# esp32.net
KiCad netlist of a schematic drawn in Altium Designer
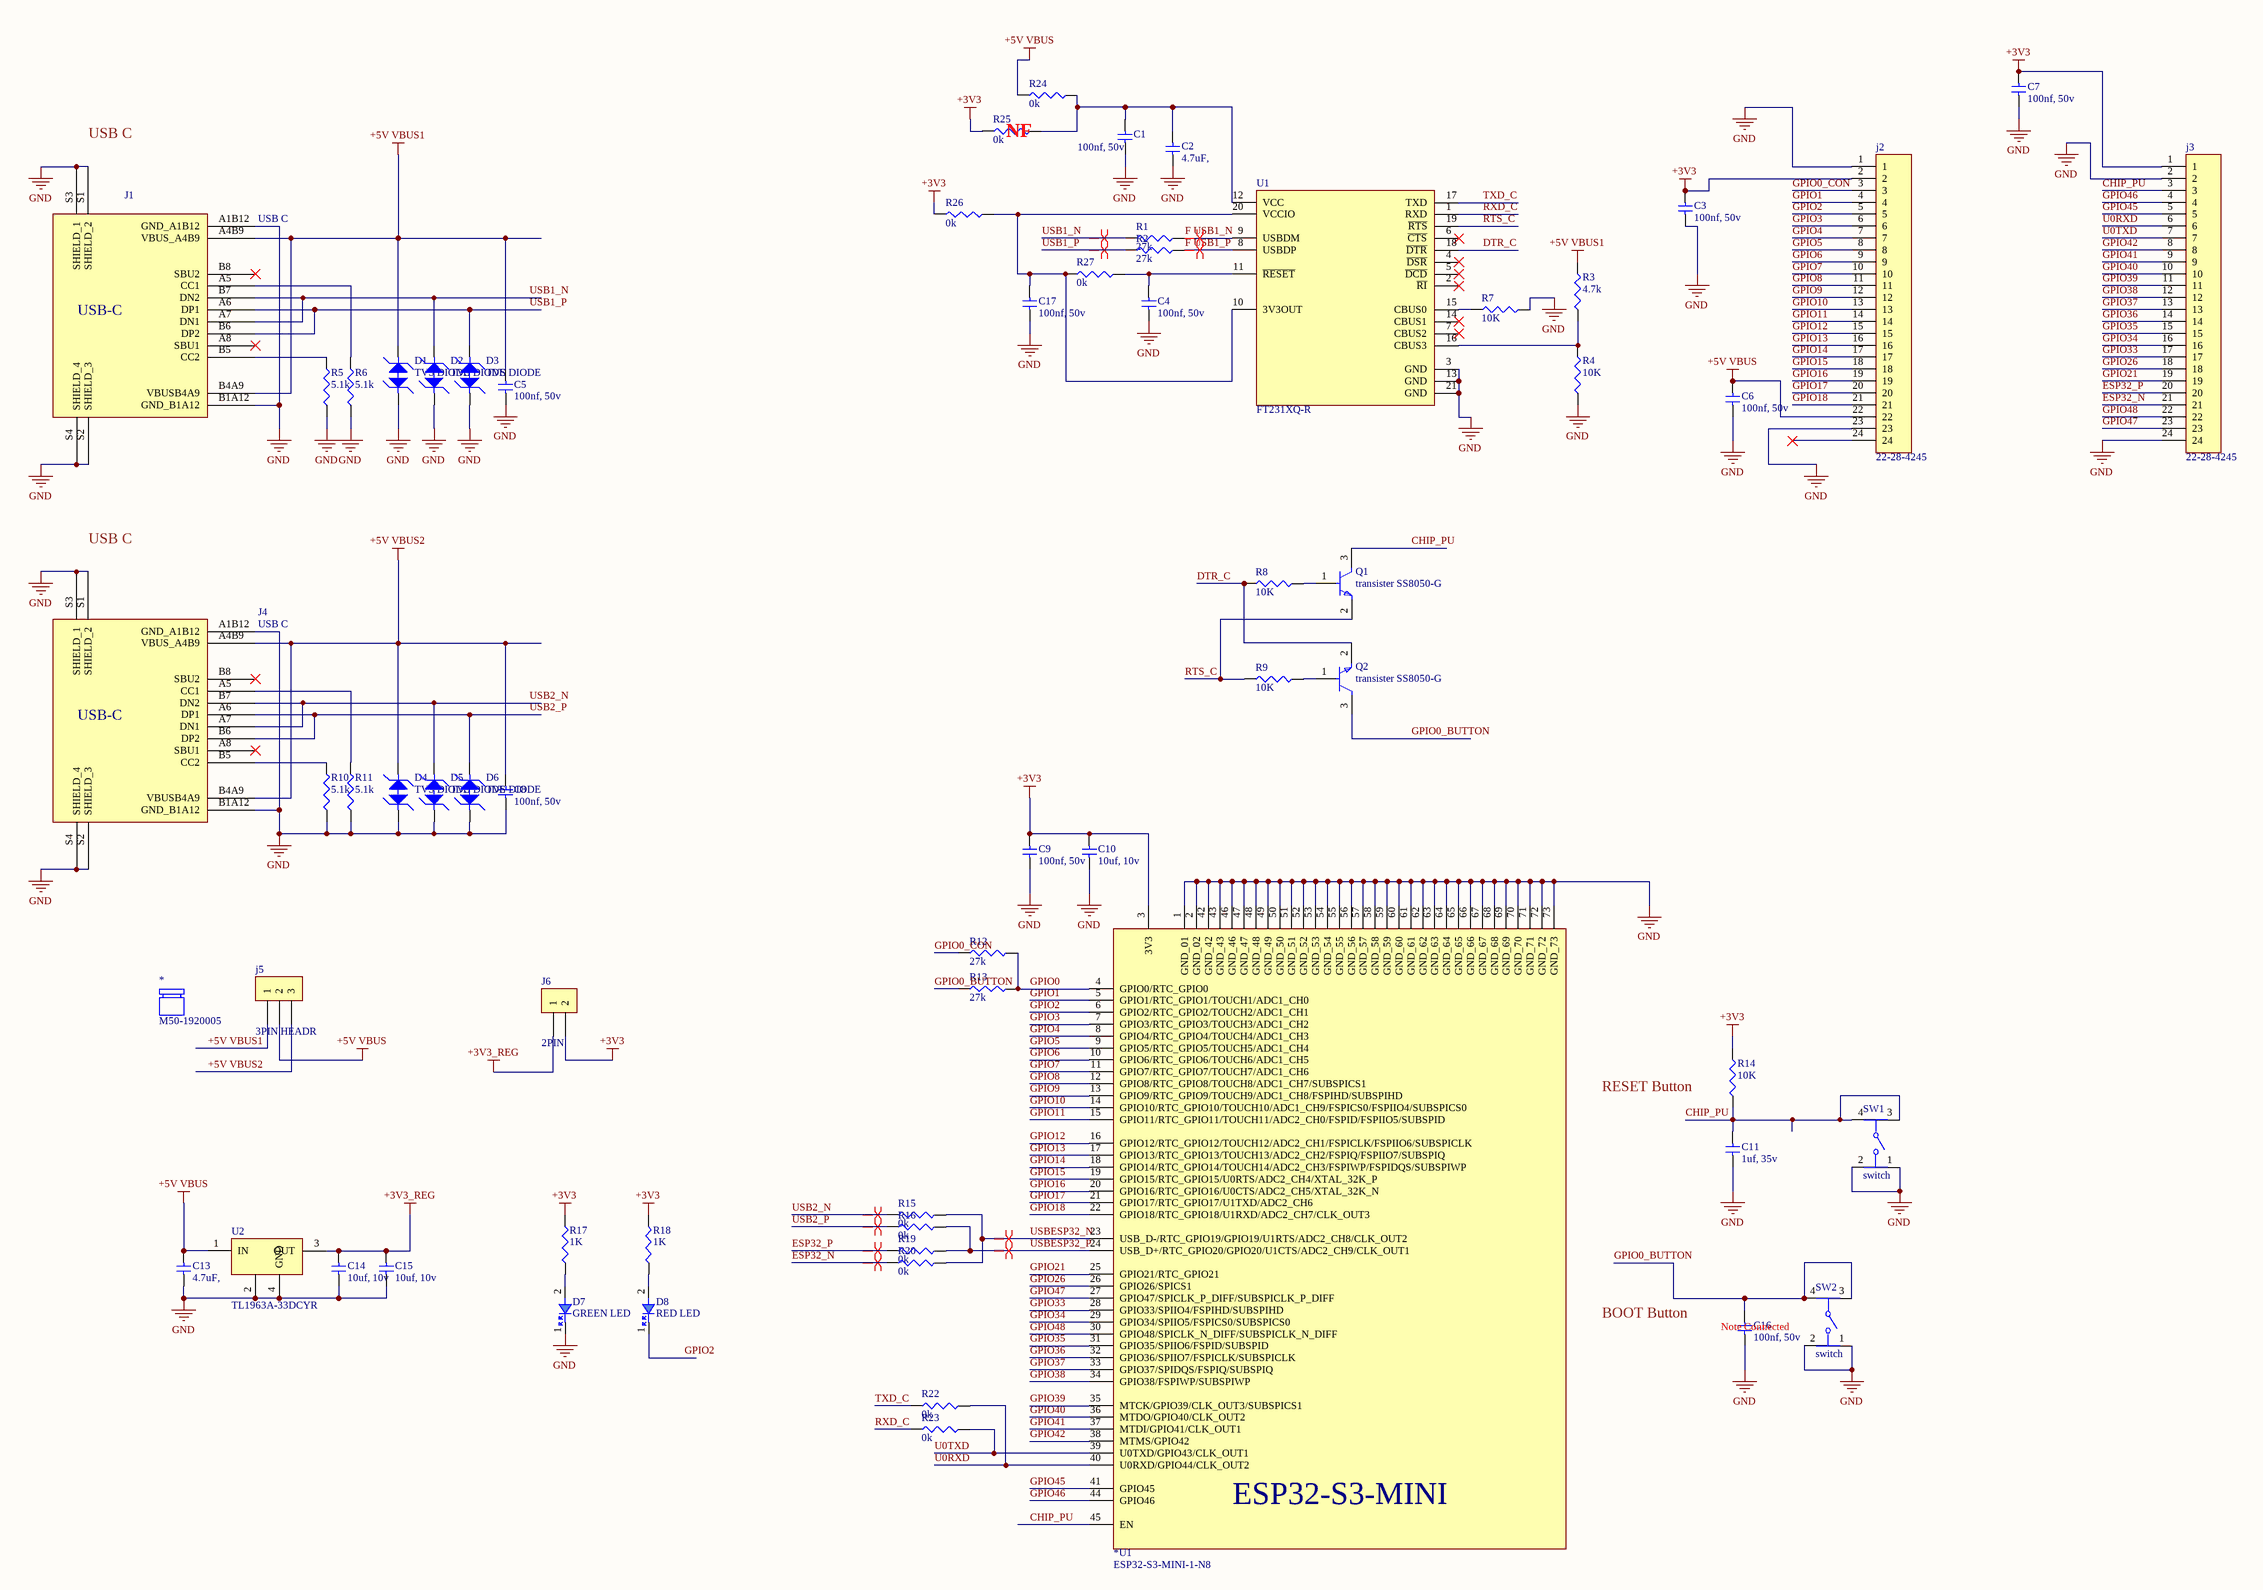
[diagram p0: esp32.SchDoc]

(export (version "E")
  (design (tool "Eeschema 10.0.6"))
  (components
    (comp (ref "*")
      (value "M50-1920005")
      (description "Interconnection Device")
      (fields (field (name "MANUFACTURER") "Harwin"))
      (libsource (lib "esp32") (part "M50-1920005"))
    )
    (comp (ref "*U1")
      (value "ESP32-S3-MINI-1-N8")
      (footprint "ESP32-S3-MINI-1-N8")
      (description "ESP32-S3FN8, 8 MB SPI flash, PCB antenna")
      (fields (field (name "MANUFACTURER") "Espressif Systems") (field (name "LCSC PART NUMBER") "C2913206"))
      (libsource (lib "esp32") (part "ESP32-S3-MINI-1-N8"))
    )
    (comp (ref "C1")
      (value "100nf, 50v")
      (footprint "CAPC1005X06N")
      (description "50V,  0.1uF, Surface Mount, 0402")
      (fields
        (field (name "MANUFACTURER") "Samsung")
        (field (name "MANUFACTURER PART NUMBER") "CL05B104KB5NNNC")
      )
      (libsource (lib "esp32") (part "CL05B104KB5NNNC"))
    )
    (comp (ref "C2")
      (value "4.7uF,")
      (footprint "CAPC1005X06N")
      (fields
        (field (name "MANUFACTURER") "Samsung")
        (field (name "MANUFACTURER PART NUMBER") "CL05A475MO5NUNC")
      )
      (libsource (lib "esp32") (part "CL05A475MO5NUNC"))
    )
    (comp (ref "C3")
      (value "100nf, 50v")
      (footprint "CAPC1005X06N")
      (description "50V,  0.1uF, Surface Mount, 0402")
      (fields
        (field (name "MANUFACTURER") "Samsung")
        (field (name "MANUFACTURER PART NUMBER") "CL05B104KB5NNNC")
      )
      (libsource (lib "esp32") (part "CL05B104KB5NNNC"))
    )
    (comp (ref "C4")
      (value "100nf, 50v")
      (footprint "CAPC1005X06N")
      (description "50V,  0.1uF, Surface Mount, 0402")
      (fields
        (field (name "MANUFACTURER") "Samsung")
        (field (name "MANUFACTURER PART NUMBER") "CL05B104KB5NNNC")
      )
      (libsource (lib "esp32") (part "CL05B104KB5NNNC"))
    )
    (comp (ref "C5")
      (value "100nf, 50v")
      (footprint "CAPC1005X06N")
      (description "50V,  0.1uF, Surface Mount, 0402")
      (fields
        (field (name "MANUFACTURER") "Samsung")
        (field (name "MANUFACTURER PART NUMBER") "CL05B104KB5NNNC")
      )
      (libsource (lib "esp32") (part "CL05B104KB5NNNC"))
    )
    (comp (ref "C6")
      (value "100nf, 50v")
      (footprint "CAPC1005X06N")
      (description "50V,  0.1uF, Surface Mount, 0402")
      (fields
        (field (name "MANUFACTURER") "Samsung")
        (field (name "MANUFACTURER PART NUMBER") "CL05B104KB5NNNC")
      )
      (libsource (lib "esp32") (part "CL05B104KB5NNNC"))
    )
    (comp (ref "C7")
      (value "100nf, 50v")
      (footprint "CAPC1005X06N")
      (description "50V,  0.1uF, Surface Mount, 0402")
      (fields
        (field (name "MANUFACTURER") "Samsung")
        (field (name "MANUFACTURER PART NUMBER") "CL05B104KB5NNNC")
      )
      (libsource (lib "esp32") (part "CL05B104KB5NNNC"))
    )
    (comp (ref "C8")
      (value "100nf, 50v")
      (footprint "CAPC1005X06N")
      (description "50V,  0.1uF, Surface Mount, 0402")
      (fields
        (field (name "MANUFACTURER") "Samsung")
        (field (name "MANUFACTURER PART NUMBER") "CL05B104KB5NNNC")
      )
      (libsource (lib "esp32") (part "CL05B104KB5NNNC"))
    )
    (comp (ref "C9")
      (value "100nf, 50v")
      (footprint "CAPC1005X06N")
      (description "50V,  0.1uF, Surface Mount, 0402")
      (fields
        (field (name "MANUFACTURER") "Samsung")
        (field (name "MANUFACTURER PART NUMBER") "CL05B104KB5NNNC")
      )
      (libsource (lib "esp32") (part "CL05B104KB5NNNC"))
    )
    (comp (ref "C10")
      (value "10uf, 10v")
      (footprint "CAPC1005X06N")
      (description "10V,10uF, Surface Mount, 0402")
      (fields
        (field (name "MANUFACTURER") "Samsung")
        (field (name "MANUFACTURER PART NUMBER") "CL05A106MP5NRNC")
      )
      (libsource (lib "esp32") (part "CL05A106MP5NRNC"))
    )
    (comp (ref "C11")
      (value "1uf, 35v")
      (footprint "CAPC1005X06N")
      (description "35V, 1uF, Surface Mount, 0402")
      (fields
        (field (name "MANUFACTURER") "Samsung")
        (field (name "MANUFACTURER PART NUMBER") "CL05A105KL5NRNC")
      )
      (libsource (lib "esp32") (part "CL05A105KL5NRNC"))
    )
    (comp (ref "C13")
      (value "4.7uF,")
      (footprint "CAPC1005X06N")
      (fields
        (field (name "MANUFACTURER") "Samsung")
        (field (name "MANUFACTURER PART NUMBER") "CL05A475MO5NUNC")
      )
      (libsource (lib "esp32") (part "CL05A475MO5NUNC"))
    )
    (comp (ref "C14")
      (value "10uf, 10v")
      (footprint "CAPC1005X06N")
      (description "10V,10uF, Surface Mount, 0402")
      (fields
        (field (name "MANUFACTURER") "Samsung")
        (field (name "MANUFACTURER PART NUMBER") "CL05A106MP5NRNC")
      )
      (libsource (lib "esp32") (part "CL05A106MP5NRNC"))
    )
    (comp (ref "C15")
      (value "10uf, 10v")
      (footprint "CAPC1005X06N")
      (description "10V,10uF, Surface Mount, 0402")
      (fields
        (field (name "MANUFACTURER") "Samsung")
        (field (name "MANUFACTURER PART NUMBER") "CL05A106MP5NRNC")
      )
      (libsource (lib "esp32") (part "CL05A106MP5NRNC"))
    )
    (comp (ref "C16")
      (value "100nf, 50v")
      (footprint "CAPC1005X06N")
      (description "50V,  0.1uF, Surface Mount, 0402")
      (fields
        (field (name "MANUFACTURER") "Samsung")
        (field (name "MANUFACTURER PART NUMBER") "CL05B104KB5NNNC")
      )
      (libsource (lib "esp32") (part "CL05B104KB5NNNC"))
    )
    (comp (ref "C17")
      (value "100nf, 50v")
      (footprint "CAPC1005X06N")
      (description "50V,  0.1uF, Surface Mount, 0402")
      (fields
        (field (name "MANUFACTURER") "Samsung")
        (field (name "MANUFACTURER PART NUMBER") "CL05B104KB5NNNC")
      )
      (libsource (lib "esp32") (part "CL05B104KB5NNNC"))
    )
    (comp (ref "D1")
      (value "TVS DIODE")
      (footprint "tv Diode")
      (description "Trans Voltage Suppressor Diode, 40W, 5.3V V(RWM), Bidirectional, 1 Element, Silicon, MO-236")
      (fields
        (field (name "MANUFACTURER") "Littelfuse")
        (field (name "MANUFACTURER PART NUMBER") "AQ3045-01ETG")
      )
      (libsource (lib "esp32") (part "AQ3045-01ETG"))
    )
    (comp (ref "D2")
      (value "TVS DIODE")
      (footprint "tv Diode")
      (description "Trans Voltage Suppressor Diode, 40W, 5.3V V(RWM), Bidirectional, 1 Element, Silicon, MO-236")
      (fields
        (field (name "MANUFACTURER") "Littelfuse")
        (field (name "MANUFACTURER PART NUMBER") "AQ3045-01ETG")
      )
      (libsource (lib "esp32") (part "AQ3045-01ETG"))
    )
    (comp (ref "D3")
      (value "TVS DIODE")
      (footprint "tv Diode")
      (description "Trans Voltage Suppressor Diode, 40W, 5.3V V(RWM), Bidirectional, 1 Element, Silicon, MO-236")
      (fields
        (field (name "MANUFACTURER") "Littelfuse")
        (field (name "MANUFACTURER PART NUMBER") "AQ3045-01ETG")
      )
      (libsource (lib "esp32") (part "AQ3045-01ETG"))
    )
    (comp (ref "D4")
      (value "TVS DIODE")
      (footprint "tv Diode")
      (description "Trans Voltage Suppressor Diode, 40W, 5.3V V(RWM), Bidirectional, 1 Element, Silicon, MO-236")
      (fields
        (field (name "MANUFACTURER") "Littelfuse")
        (field (name "MANUFACTURER PART NUMBER") "AQ3045-01ETG")
      )
      (libsource (lib "esp32") (part "AQ3045-01ETG"))
    )
    (comp (ref "D5")
      (value "TVS DIODE")
      (footprint "tv Diode")
      (description "Trans Voltage Suppressor Diode, 40W, 5.3V V(RWM), Bidirectional, 1 Element, Silicon, MO-236")
      (fields
        (field (name "MANUFACTURER") "Littelfuse")
        (field (name "MANUFACTURER PART NUMBER") "AQ3045-01ETG")
      )
      (libsource (lib "esp32") (part "AQ3045-01ETG"))
    )
    (comp (ref "D6")
      (value "TVS DIODE")
      (footprint "tv Diode")
      (description "Trans Voltage Suppressor Diode, 40W, 5.3V V(RWM), Bidirectional, 1 Element, Silicon, MO-236")
      (fields
        (field (name "MANUFACTURER") "Littelfuse")
        (field (name "MANUFACTURER PART NUMBER") "AQ3045-01ETG")
      )
      (libsource (lib "esp32") (part "AQ3045-01ETG"))
    )
    (comp (ref "D7")
      (value "GREEN LED")
      (footprint "led green")
      (description "Single Color LED, Yellow Green, 0.5mm")
      (fields
        (field (name "MANUFACTURER") "Vishay")
        (field (name "MANUFACTURER PART NUMBER") "VLMG1500-GS08")
      )
      (libsource (lib "esp32") (part "VLMG1500-GS08"))
    )
    (comp (ref "D8")
      (value "RED LED")
      (footprint "red led")
      (description "Single Color LED, Yellow Green, 0.5mm")
      (fields
        (field (name "MANUFACTURER") "Vishay")
        (field (name "MANUFACTURER PART NUMBER") "VLMG1500-GS08")
      )
      (libsource (lib "esp32") (part "VLMG1500-GS08_1"))
    )
    (comp (ref "J1")
      (value "USB C")
      (footprint "usb_c")
      (description "USB Connector, 16 Contact(s), Female, Right Angle, Surface Mount Terminal, Locking, Receptacle")
      (fields (field (name "MANUFACTURER") "Molex") (field (name "MANUFACTURER PART NUMBER") "217179-0001"))
      (libsource (lib "esp32") (part "217179-0001"))
    )
    (comp (ref "j2")
      (value "22-28-4245")
      (footprint "pin 24 2.54mm")
      (description "Conn Unshrouded Header HDR 24 POS 2.54mm Solder ST Thru-Hole KK® Bag")
      (fields (field (name "MANUFACTURER") "Molex"))
      (libsource (lib "esp32") (part "22-28-4245"))
    )
    (comp (ref "j3")
      (value "22-28-4245")
      (footprint "pin 24 2.54mm")
      (description "Conn Unshrouded Header HDR 24 POS 2.54mm Solder ST Thru-Hole KK® Bag")
      (fields (field (name "MANUFACTURER") "Molex"))
      (libsource (lib "esp32") (part "22-28-4245"))
    )
    (comp (ref "J4")
      (value "USB C")
      (footprint "usb_c")
      (description "USB Connector, 16 Contact(s), Female, Right Angle, Surface Mount Terminal, Locking, Receptacle")
      (fields (field (name "MANUFACTURER") "Molex") (field (name "MANUFACTURER PART NUMBER") "217179-0001"))
      (libsource (lib "esp32") (part "217179-0001"))
    )
    (comp (ref "j5")
      (value "3PIN HEADR")
      (footprint "pin3")
      (description "Board Connector, 3 Contact(s), 1 Row(s), Male, Straight, Solder Terminal")
      (fields
        (field (name "MANUFACTURER") "Samtec")
        (field (name "MANUFACTURER PART NUMBER") "FTS-103-01-F-S")
      )
      (libsource (lib "esp32") (part "FTS-103-01-F-S"))
    )
    (comp (ref "J6")
      (value "2PIN")
      (footprint "pin2")
      (description "Board Connector, 2 Contact(s), 1 Row(s), Male, Straight, Solder Terminal")
      (fields
        (field (name "MANUFACTURER") "Samtec")
        (field (name "MANUFACTURER PART NUMBER") "FTS-102-01-F-S")
      )
      (libsource (lib "esp32") (part "FTS-102-01-F-S"))
    )
    (comp (ref "Q1")
      (value "transister SS8050-G")
      (footprint "transister")
      (description "Small Signal Bipolar Transistor, 1.5A I(C), 25V V(BR)CEO, 1-Element, NPN, Silicon")
      (fields (field (name "MANUFACTURER") "Comchip") (field (name "MANUFACTURER PART NUMBER") "SS8050-G"))
      (libsource (lib "esp32") (part "SS8050-G"))
    )
    (comp (ref "Q2")
      (value "transister SS8050-G")
      (footprint "transister")
      (description "Small Signal Bipolar Transistor, 1.5A I(C), 25V V(BR)CEO, 1-Element, NPN, Silicon")
      (fields (field (name "MANUFACTURER") "Comchip") (field (name "MANUFACTURER PART NUMBER") "SS8050-G"))
      (libsource (lib "esp32") (part "SS8050-G"))
    )
    (comp (ref "R1")
      (value "27k")
      (footprint "RESC1005X04N")
      (description "27k,Fixed Resistor 0.0625W, , 50V, Surface Mount, 0402")
      (fields
        (field (name "MANUFACTURER") "Yageo")
        (field (name "MANUFACTURER PART NUMBER") "AC0402FR-0727KL")
      )
      (libsource (lib "esp32") (part "AC0402FR-0727KL"))
    )
    (comp (ref "R2")
      (value "27k")
      (footprint "RESC1005X04N")
      (description "27k,Fixed Resistor 0.0625W, , 50V, Surface Mount, 0402")
      (fields
        (field (name "MANUFACTURER") "Yageo")
        (field (name "MANUFACTURER PART NUMBER") "AC0402FR-0727KL")
      )
      (libsource (lib "esp32") (part "AC0402FR-0727KL"))
    )
    (comp (ref "R3")
      (value "4.7k")
      (footprint "RESC1005X04N")
      (fields
        (field (name "MANUFACTURER") "Yageo")
        (field (name "MANUFACTURER PART NUMBER") "RC0402JR-074K7L")
        (field (name "TOLERANCE") "5%")
      )
      (libsource (lib "esp32") (part "RC0402JR-074K7L"))
    )
    (comp (ref "R4")
      (value "10K")
      (footprint "RESC1005X04N")
      (description "0.125W, 10kohm, 75V, Surface Mount, 0402")
      (fields
        (field (name "MANUFACTURER") "Yageo")
        (field (name "MANUFACTURER PART NUMBER") "AC0402FR-7W10KL")
      )
      (libsource (lib "esp32") (part "AC0402FR-7W10KL"))
    )
    (comp (ref "R5")
      (value "5.1k")
      (footprint "RESC1005X04N")
      (description "Resistor 0.0625W, 5.1Kohm, 50V, 1% +/-Tol, 100ppm/Cel, Surface Mount, 0402")
      (fields
        (field (name "MANUFACTURER") "Yageo")
        (field (name "MANUFACTURER PART NUMBER") "AC0402FR-075K1L")
      )
      (libsource (lib "esp32") (part "AC0402FR-075K1L"))
    )
    (comp (ref "R6")
      (value "5.1k")
      (footprint "RESC1005X04N")
      (description "Resistor 0.0625W, 5.1Kohm, 50V, 1% +/-Tol, 100ppm/Cel, Surface Mount, 0402")
      (fields
        (field (name "MANUFACTURER") "Yageo")
        (field (name "MANUFACTURER PART NUMBER") "AC0402FR-075K1L")
      )
      (libsource (lib "esp32") (part "AC0402FR-075K1L"))
    )
    (comp (ref "R7")
      (value "10K")
      (footprint "RESC1005X04N")
      (description "0.125W, 10kohm, 75V, Surface Mount, 0402")
      (fields
        (field (name "MANUFACTURER") "Yageo")
        (field (name "MANUFACTURER PART NUMBER") "AC0402FR-7W10KL")
      )
      (libsource (lib "esp32") (part "AC0402FR-7W10KL"))
    )
    (comp (ref "R8")
      (value "10K")
      (footprint "RESC1005X04N")
      (description "0.125W, 10kohm, 75V, Surface Mount, 0402")
      (fields
        (field (name "MANUFACTURER") "Yageo")
        (field (name "MANUFACTURER PART NUMBER") "AC0402FR-7W10KL")
      )
      (libsource (lib "esp32") (part "AC0402FR-7W10KL"))
    )
    (comp (ref "R9")
      (value "10K")
      (footprint "RESC1005X04N")
      (description "0.125W, 10kohm, 75V, Surface Mount, 0402")
      (fields
        (field (name "MANUFACTURER") "Yageo")
        (field (name "MANUFACTURER PART NUMBER") "AC0402FR-7W10KL")
      )
      (libsource (lib "esp32") (part "AC0402FR-7W10KL"))
    )
    (comp (ref "R10")
      (value "5.1k")
      (footprint "RESC1005X04N")
      (description "Resistor 0.0625W, 5.1Kohm, 50V, 1% +/-Tol, 100ppm/Cel, Surface Mount, 0402")
      (fields
        (field (name "MANUFACTURER") "Yageo")
        (field (name "MANUFACTURER PART NUMBER") "AC0402FR-075K1L")
      )
      (libsource (lib "esp32") (part "AC0402FR-075K1L"))
    )
    (comp (ref "R11")
      (value "5.1k")
      (footprint "RESC1005X04N")
      (description "Resistor 0.0625W, 5.1Kohm, 50V, 1% +/-Tol, 100ppm/Cel, Surface Mount, 0402")
      (fields
        (field (name "MANUFACTURER") "Yageo")
        (field (name "MANUFACTURER PART NUMBER") "AC0402FR-075K1L")
      )
      (libsource (lib "esp32") (part "AC0402FR-075K1L"))
    )
    (comp (ref "R12")
      (value "27k")
      (footprint "RESC1005X04N")
      (description "27k,Fixed Resistor 0.0625W, , 50V, Surface Mount, 0402")
      (fields
        (field (name "MANUFACTURER") "Yageo")
        (field (name "MANUFACTURER PART NUMBER") "AC0402FR-0727KL")
      )
      (libsource (lib "esp32") (part "AC0402FR-0727KL"))
    )
    (comp (ref "R13")
      (value "27k")
      (footprint "RESC1005X04N")
      (description "27k,Fixed Resistor 0.0625W, , 50V, Surface Mount, 0402")
      (fields
        (field (name "MANUFACTURER") "Yageo")
        (field (name "MANUFACTURER PART NUMBER") "AC0402FR-0727KL")
      )
      (libsource (lib "esp32") (part "AC0402FR-0727KL"))
    )
    (comp (ref "R14")
      (value "10K")
      (footprint "RESC1005X04N")
      (description "0.125W, 10kohm, 75V, Surface Mount, 0402")
      (fields
        (field (name "MANUFACTURER") "Yageo")
        (field (name "MANUFACTURER PART NUMBER") "AC0402FR-7W10KL")
      )
      (libsource (lib "esp32") (part "AC0402FR-7W10KL"))
    )
    (comp (ref "R15")
      (value "0k")
      (footprint "RESC1005X04N")
      (description "0.0625W, 0ohm, Surface Mount, 0402")
      (fields
        (field (name "MANUFACTURER") "Yageo")
        (field (name "MANUFACTURER PART NUMBER") "RC0402FR-070RL")
      )
      (libsource (lib "esp32") (part "RC0402FR-070RL"))
    )
    (comp (ref "R16")
      (value "0k")
      (footprint "RESC1005X04N")
      (description "0.0625W, 0ohm, Surface Mount, 0402")
      (fields
        (field (name "MANUFACTURER") "Yageo")
        (field (name "MANUFACTURER PART NUMBER") "RC0402FR-070RL")
      )
      (libsource (lib "esp32") (part "RC0402FR-070RL"))
    )
    (comp (ref "R17")
      (value "1K")
      (footprint "RESC1005X04N")
      (fields
        (field (name "MANUFACTURER") "Yageo")
        (field (name "MANUFACTURER PART NUMBER") "RC0402FR-071KL")
        (field (name "TOLERANCE") "1%")
      )
      (libsource (lib "esp32") (part "RC0402FR-071KL"))
    )
    (comp (ref "R18")
      (value "1K")
      (footprint "RESC1005X04N")
      (fields
        (field (name "MANUFACTURER") "Yageo")
        (field (name "MANUFACTURER PART NUMBER") "RC0402FR-071KL")
        (field (name "TOLERANCE") "1%")
      )
      (libsource (lib "esp32") (part "RC0402FR-071KL"))
    )
    (comp (ref "R19")
      (value "0k")
      (footprint "RESC1005X04N")
      (description "0.0625W, 0ohm, Surface Mount, 0402")
      (fields
        (field (name "MANUFACTURER") "Yageo")
        (field (name "MANUFACTURER PART NUMBER") "RC0402FR-070RL")
      )
      (libsource (lib "esp32") (part "RC0402FR-070RL"))
    )
    (comp (ref "R20")
      (value "0k")
      (footprint "RESC1005X04N")
      (description "0.0625W, 0ohm, Surface Mount, 0402")
      (fields
        (field (name "MANUFACTURER") "Yageo")
        (field (name "MANUFACTURER PART NUMBER") "RC0402FR-070RL")
      )
      (libsource (lib "esp32") (part "RC0402FR-070RL"))
    )
    (comp (ref "R22")
      (value "0k")
      (footprint "RESC1005X04N")
      (description "0.0625W, 0ohm, Surface Mount, 0402")
      (fields
        (field (name "MANUFACTURER") "Yageo")
        (field (name "MANUFACTURER PART NUMBER") "RC0402FR-070RL")
      )
      (libsource (lib "esp32") (part "RC0402FR-070RL"))
    )
    (comp (ref "R23")
      (value "0k")
      (footprint "RESC1005X04N")
      (description "0.0625W, 0ohm, Surface Mount, 0402")
      (fields
        (field (name "MANUFACTURER") "Yageo")
        (field (name "MANUFACTURER PART NUMBER") "RC0402FR-070RL")
      )
      (libsource (lib "esp32") (part "RC0402FR-070RL"))
    )
    (comp (ref "R24")
      (value "0k")
      (footprint "RESC1005X04N")
      (description "0.0625W, 0ohm, Surface Mount, 0402")
      (fields
        (field (name "MANUFACTURER") "Yageo")
        (field (name "MANUFACTURER PART NUMBER") "RC0402FR-070RL")
      )
      (libsource (lib "esp32") (part "RC0402FR-070RL"))
    )
    (comp (ref "R25")
      (value "0k")
      (footprint "RESC1005X04N")
      (description "0.0625W, 0ohm, Surface Mount, 0402")
      (fields
        (field (name "MANUFACTURER") "Yageo")
        (field (name "MANUFACTURER PART NUMBER") "RC0402FR-070RL")
      )
      (libsource (lib "esp32") (part "RC0402FR-070RL"))
    )
    (comp (ref "R26")
      (value "0k")
      (footprint "RESC1005X04N")
      (description "0.0625W, 0ohm, Surface Mount, 0402")
      (fields
        (field (name "MANUFACTURER") "Yageo")
        (field (name "MANUFACTURER PART NUMBER") "RC0402FR-070RL")
      )
      (libsource (lib "esp32") (part "RC0402FR-070RL"))
    )
    (comp (ref "R27")
      (value "0k")
      (footprint "RESC1005X04N")
      (description "0.0625W, 0ohm, Surface Mount, 0402")
      (fields
        (field (name "MANUFACTURER") "Yageo")
        (field (name "MANUFACTURER PART NUMBER") "RC0402FR-070RL")
      )
      (libsource (lib "esp32") (part "RC0402FR-070RL"))
    )
    (comp (ref "SW1")
      (value "switch")
      (footprint "button")
      (description "Keypad Switch, 0.05A, 12VDC, 2.55N, , Surface Mount-straight")
      (fields
        (field (name "MANUFACTURER") "ITT C&K")
        (field (name "MANUFACTURER PART NUMBER") "PTS645SK43SMTR92LFS")
      )
      (libsource (lib "esp32") (part "PTS645SK43SMTR92LFS"))
    )
    (comp (ref "SW2")
      (value "switch")
      (footprint "button")
      (description "Keypad Switch, 0.05A, 12VDC, 2.55N, , Surface Mount-straight")
      (fields
        (field (name "MANUFACTURER") "ITT C&K")
        (field (name "MANUFACTURER PART NUMBER") "PTS645SK43SMTR92LFS")
      )
      (libsource (lib "esp32") (part "PTS645SK43SMTR92LFS"))
    )
    (comp (ref "U1")
      (value "FT231XQ-R")
      (footprint "QFN50P400X400X80_HS-21N")
      (description "IC USB SERIAL FULL UART 20QFN")
      (fields (field (name "MANUFACTURER") "FTDI"))
      (libsource (lib "esp32") (part "FT231XQ-R"))
    )
    (comp (ref "U2")
      (value "TL1963A-33DCYR")
      (footprint "SOT230P700X180-4N")
      (description "Fixed Positive LDO Regulator, 3.3V, 0.55V Dropout, BIPolar, PDSO4")
      (fields (field (name "MANUFACTURER") "Texas Instruments"))
      (libsource (lib "esp32") (part "Regulato TL1963A-33DCYR"))
    )
  )
  (nets
    (net (code "1") (name "+3V3") (class "Default")
      (node (ref "*U1") (pin "3") (pinfunction "3V3_3") (pintype "passive"))
      (node (ref "C10") (pin "2") (pinfunction "2_2") (pintype "open_collector"))
      (node (ref "C3") (pin "2") (pinfunction "2_2") (pintype "open_collector"))
      (node (ref "C7") (pin "2") (pinfunction "2_2") (pintype "open_collector"))
      (node (ref "C9") (pin "2") (pinfunction "2_2") (pintype "open_collector"))
      (node (ref "J6") (pin "2") (pinfunction "2_2") (pintype "open_collector"))
      (node (ref "R14") (pin "2") (pinfunction "2_2") (pintype "open_collector"))
      (node (ref "R17") (pin "2") (pinfunction "2_2") (pintype "open_collector"))
      (node (ref "R18") (pin "2") (pinfunction "2_2") (pintype "open_collector"))
      (node (ref "R25") (pin "1") (pinfunction "1_1") (pintype "open_collector"))
      (node (ref "R26") (pin "1") (pinfunction "1_1") (pintype "open_collector"))
      (node (ref "j2") (pin "2") (pinfunction "2_2") (pintype "passive"))
      (node (ref "j3") (pin "1") (pinfunction "1_1") (pintype "passive"))
    )
    (net (code "2") (name "+3V3_REG") (class "Default")
      (node (ref "C14") (pin "2") (pinfunction "2_2") (pintype "open_collector"))
      (node (ref "C15") (pin "2") (pinfunction "2_2") (pintype "open_collector"))
      (node (ref "J6") (pin "1") (pinfunction "1_1") (pintype "open_collector"))
      (node (ref "U2") (pin "3") (pinfunction "OUT_3") (pintype "passive"))
    )
    (net (code "3") (name "+5V VBUS") (class "Default")
      (node (ref "C13") (pin "2") (pinfunction "2_2") (pintype "open_collector"))
      (node (ref "C6") (pin "2") (pinfunction "2_2") (pintype "open_collector"))
      (node (ref "R24") (pin "1") (pinfunction "1_1") (pintype "open_collector"))
      (node (ref "U2") (pin "1") (pinfunction "IN_1") (pintype "passive"))
      (node (ref "j2") (pin "22") (pinfunction "22_22") (pintype "passive"))
      (node (ref "j5") (pin "2") (pinfunction "2_2") (pintype "open_collector"))
    )
    (net (code "4") (name "+5V VBUS1") (class "Default")
      (node (ref "C5") (pin "2") (pinfunction "2_2") (pintype "open_collector"))
      (node (ref "D1") (pin "2") (pinfunction "2_2") (pintype "open_collector"))
      (node (ref "J1") (pin "A4B9") (pinfunction "VBUS_A4B9_A4B9") (pintype "passive"))
      (node (ref "J1") (pin "B4A9") (pinfunction "VBUSB4A9_B4A9") (pintype "passive"))
      (node (ref "R3") (pin "2") (pinfunction "2_2") (pintype "open_collector"))
      (node (ref "j5") (pin "1") (pinfunction "1_1") (pintype "open_collector"))
    )
    (net (code "5") (name "+5V VBUS2") (class "Default")
      (node (ref "C8") (pin "2") (pinfunction "2_2") (pintype "open_collector"))
      (node (ref "D4") (pin "2") (pinfunction "2_2") (pintype "open_collector"))
      (node (ref "J4") (pin "A4B9") (pinfunction "VBUS_A4B9_A4B9") (pintype "passive"))
      (node (ref "J4") (pin "B4A9") (pinfunction "VBUSB4A9_B4A9") (pintype "passive"))
      (node (ref "j5") (pin "3") (pinfunction "3_3") (pintype "open_collector"))
    )
    (net (code "6") (name "/CHIP_PU") (class "Default")
      (node (ref "*U1") (pin "45") (pinfunction "EN_45") (pintype "passive"))
      (node (ref "C11") (pin "2") (pinfunction "2_2") (pintype "open_collector"))
      (node (ref "Q1") (pin "3") (pinfunction "C_3") (pintype "passive"))
      (node (ref "R14") (pin "1") (pinfunction "1_1") (pintype "open_collector"))
      (node (ref "SW1") (pin "3") (pinfunction "3_3") (pintype "passive"))
      (node (ref "SW1") (pin "4") (pinfunction "4_4") (pintype "passive"))
      (node (ref "j3") (pin "3") (pinfunction "3_3") (pintype "passive"))
    )
    (net (code "7") (name "/DTR_C") (class "Default")
      (node (ref "Q2") (pin "2") (pinfunction "E_2") (pintype "passive"))
      (node (ref "R8") (pin "1") (pinfunction "1_1") (pintype "open_collector"))
      (node (ref "U1") (pin "18") (pinfunction "~{DTR}_18") (pintype "passive"))
    )
    (net (code "8") (name "/ESP32_N") (class "Default")
      (node (ref "R20") (pin "1") (pinfunction "1_1") (pintype "open_collector"))
      (node (ref "j3") (pin "21") (pinfunction "21_21") (pintype "passive"))
    )
    (net (code "9") (name "/ESP32_P") (class "Default")
      (node (ref "R19") (pin "1") (pinfunction "1_1") (pintype "open_collector"))
      (node (ref "j3") (pin "20") (pinfunction "20_20") (pintype "passive"))
    )
    (net (code "10") (name "/F USB1_N") (class "Default")
      (node (ref "R1") (pin "2") (pinfunction "2_2") (pintype "open_collector"))
      (node (ref "U1") (pin "9") (pinfunction "USBDM_9") (pintype "passive"))
    )
    (net (code "11") (name "/F USB1_P") (class "Default")
      (node (ref "R2") (pin "2") (pinfunction "2_2") (pintype "open_collector"))
      (node (ref "U1") (pin "8") (pinfunction "USBDP_8") (pintype "passive"))
    )
    (net (code "12") (name "/GPIO0") (class "Default")
      (node (ref "*U1") (pin "4") (pinfunction "GPIO0/RTC_GPIO0_4") (pintype "passive"))
      (node (ref "R12") (pin "2") (pinfunction "2_2") (pintype "open_collector"))
      (node (ref "R13") (pin "2") (pinfunction "2_2") (pintype "open_collector"))
    )
    (net (code "13") (name "/GPIO0_BUTTON") (class "Default")
      (node (ref "C16") (pin "2") (pinfunction "2_2") (pintype "open_collector"))
      (node (ref "Q2") (pin "3") (pinfunction "C_3") (pintype "passive"))
      (node (ref "R13") (pin "1") (pinfunction "1_1") (pintype "open_collector"))
      (node (ref "SW2") (pin "3") (pinfunction "3_3") (pintype "passive"))
      (node (ref "SW2") (pin "4") (pinfunction "4_4") (pintype "passive"))
    )
    (net (code "14") (name "/GPIO0_CON") (class "Default")
      (node (ref "R12") (pin "1") (pinfunction "1_1") (pintype "open_collector"))
      (node (ref "j2") (pin "3") (pinfunction "3_3") (pintype "passive"))
    )
    (net (code "15") (name "/GPIO1") (class "Default")
      (node (ref "*U1") (pin "5") (pinfunction "GPIO1/RTC_GPIO1/TOUCH1/ADC1_CH0_5") (pintype "passive"))
      (node (ref "j2") (pin "4") (pinfunction "4_4") (pintype "passive"))
    )
    (net (code "16") (name "/GPIO2") (class "Default")
      (node (ref "*U1") (pin "6") (pinfunction "GPIO2/RTC_GPIO2/TOUCH2/ADC1_CH1_6") (pintype "passive"))
      (node (ref "D8") (pin "1") (pinfunction "1_1") (pintype "passive"))
      (node (ref "j2") (pin "5") (pinfunction "5_5") (pintype "passive"))
    )
    (net (code "17") (name "/GPIO3") (class "Default")
      (node (ref "*U1") (pin "7") (pinfunction "GPIO3/RTC_GPIO3/TOUCH3/ADC1_CH2_7") (pintype "passive"))
      (node (ref "j2") (pin "6") (pinfunction "6_6") (pintype "passive"))
    )
    (net (code "18") (name "/GPIO4") (class "Default")
      (node (ref "*U1") (pin "8") (pinfunction "GPIO4/RTC_GPIO4/TOUCH4/ADC1_CH3_8") (pintype "passive"))
      (node (ref "j2") (pin "7") (pinfunction "7_7") (pintype "passive"))
    )
    (net (code "19") (name "/GPIO5") (class "Default")
      (node (ref "*U1") (pin "9") (pinfunction "GPIO5/RTC_GPIO5/TOUCH5/ADC1_CH4_9") (pintype "passive"))
      (node (ref "j2") (pin "8") (pinfunction "8_8") (pintype "passive"))
    )
    (net (code "20") (name "/GPIO6") (class "Default")
      (node (ref "*U1") (pin "10") (pinfunction "GPIO6/RTC_GPIO6/TOUCH6/ADC1_CH5_10") (pintype "passive"))
      (node (ref "j2") (pin "9") (pinfunction "9_9") (pintype "passive"))
    )
    (net (code "21") (name "/GPIO7") (class "Default")
      (node (ref "*U1") (pin "11") (pinfunction "GPIO7/RTC_GPIO7/TOUCH7/ADC1_CH6_11") (pintype "passive"))
      (node (ref "j2") (pin "10") (pinfunction "10_10") (pintype "passive"))
    )
    (net (code "22") (name "/GPIO8") (class "Default")
      (node (ref "*U1") (pin "12") (pinfunction "GPIO8/RTC_GPIO8/TOUCH8/ADC1_CH7/SUBSPICS1_12") (pintype "passive"))
      (node (ref "j2") (pin "11") (pinfunction "11_11") (pintype "passive"))
    )
    (net (code "23") (name "/GPIO9") (class "Default")
      (node (ref "*U1") (pin "13") (pinfunction "GPIO9/RTC_GPIO9/TOUCH9/ADC1_CH8/FSPIHD/SUBSPIHD_13") (pintype "passive"))
      (node (ref "j2") (pin "12") (pinfunction "12_12") (pintype "passive"))
    )
    (net (code "24") (name "/GPIO10") (class "Default")
      (node (ref "*U1") (pin "14") (pinfunction "GPIO10/RTC_GPIO10/TOUCH10/ADC1_CH9/FSPICS0/FSPIIO4/SUBSPICS0_14") (pintype "passive"))
      (node (ref "j2") (pin "13") (pinfunction "13_13") (pintype "passive"))
    )
    (net (code "25") (name "/GPIO11") (class "Default")
      (node (ref "*U1") (pin "15") (pinfunction "GPIO11/RTC_GPIO11/TOUCH11/ADC2_CH0/FSPID/FSPIIO5/SUBSPID_15") (pintype "passive"))
      (node (ref "j2") (pin "14") (pinfunction "14_14") (pintype "passive"))
    )
    (net (code "26") (name "/GPIO12") (class "Default")
      (node (ref "*U1") (pin "16") (pinfunction "GPIO12/RTC_GPIO12/TOUCH12/ADC2_CH1/FSPICLK/FSPIIO6/SUBSPICLK_16") (pintype "passive"))
      (node (ref "j2") (pin "15") (pinfunction "15_15") (pintype "passive"))
    )
    (net (code "27") (name "/GPIO13") (class "Default")
      (node (ref "*U1") (pin "17") (pinfunction "GPIO13/RTC_GPIO13/TOUCH13/ADC2_CH2/FSPIQ/FSPIIO7/SUBSPIQ_17") (pintype "passive"))
      (node (ref "j2") (pin "16") (pinfunction "16_16") (pintype "passive"))
    )
    (net (code "28") (name "/GPIO14") (class "Default")
      (node (ref "*U1") (pin "18") (pinfunction "GPIO14/RTC_GPIO14/TOUCH14/ADC2_CH3/FSPIWP/FSPIDQS/SUBSPIWP_18") (pintype "passive"))
      (node (ref "j2") (pin "17") (pinfunction "17_17") (pintype "passive"))
    )
    (net (code "29") (name "/GPIO15") (class "Default")
      (node (ref "*U1") (pin "19") (pinfunction "GPIO15/RTC_GPIO15/U0RTS/ADC2_CH4/XTAL_32K_P_19") (pintype "passive"))
      (node (ref "j2") (pin "18") (pinfunction "18_18") (pintype "passive"))
    )
    (net (code "30") (name "/GPIO16") (class "Default")
      (node (ref "*U1") (pin "20") (pinfunction "GPIO16/RTC_GPIO16/U0CTS/ADC2_CH5/XTAL_32K_N_20") (pintype "passive"))
      (node (ref "j2") (pin "19") (pinfunction "19_19") (pintype "passive"))
    )
    (net (code "31") (name "/GPIO17") (class "Default")
      (node (ref "*U1") (pin "21") (pinfunction "GPIO17/RTC_GPIO17/U1TXD/ADC2_CH6_21") (pintype "passive"))
      (node (ref "j2") (pin "20") (pinfunction "20_20") (pintype "passive"))
    )
    (net (code "32") (name "/GPIO18") (class "Default")
      (node (ref "*U1") (pin "22") (pinfunction "GPIO18/RTC_GPIO18/U1RXD/ADC2_CH7/CLK_OUT3_22") (pintype "passive"))
      (node (ref "j2") (pin "21") (pinfunction "21_21") (pintype "passive"))
    )
    (net (code "33") (name "/GPIO21") (class "Default")
      (node (ref "*U1") (pin "25") (pinfunction "GPIO21/RTC_GPIO21_25") (pintype "passive"))
      (node (ref "j3") (pin "19") (pinfunction "19_19") (pintype "passive"))
    )
    (net (code "34") (name "/GPIO26") (class "Default")
      (node (ref "*U1") (pin "26") (pinfunction "GPIO26/SPICS1_26") (pintype "passive"))
      (node (ref "j3") (pin "18") (pinfunction "18_18") (pintype "passive"))
    )
    (net (code "35") (name "/GPIO33") (class "Default")
      (node (ref "*U1") (pin "28") (pinfunction "GPIO33/SPIIO4/FSPIHD/SUBSPIHD_28") (pintype "passive"))
      (node (ref "j3") (pin "17") (pinfunction "17_17") (pintype "passive"))
    )
    (net (code "36") (name "/GPIO34") (class "Default")
      (node (ref "*U1") (pin "29") (pinfunction "GPIO34/SPIIO5/FSPICS0/SUBSPICS0_29") (pintype "passive"))
      (node (ref "j3") (pin "16") (pinfunction "16_16") (pintype "passive"))
    )
    (net (code "37") (name "/GPIO35") (class "Default")
      (node (ref "*U1") (pin "31") (pinfunction "GPIO35/SPIIO6/FSPID/SUBSPID_31") (pintype "passive"))
      (node (ref "j3") (pin "15") (pinfunction "15_15") (pintype "passive"))
    )
    (net (code "38") (name "/GPIO36") (class "Default")
      (node (ref "*U1") (pin "32") (pinfunction "GPIO36/SPIIO7/FSPICLK/SUBSPICLK_32") (pintype "passive"))
      (node (ref "j3") (pin "14") (pinfunction "14_14") (pintype "passive"))
    )
    (net (code "39") (name "/GPIO37") (class "Default")
      (node (ref "*U1") (pin "33") (pinfunction "GPIO37/SPIDQS/FSPIQ/SUBSPIQ_33") (pintype "passive"))
      (node (ref "j3") (pin "13") (pinfunction "13_13") (pintype "passive"))
    )
    (net (code "40") (name "/GPIO38") (class "Default")
      (node (ref "*U1") (pin "34") (pinfunction "GPIO38/FSPIWP/SUBSPIWP_34") (pintype "passive"))
      (node (ref "j3") (pin "12") (pinfunction "12_12") (pintype "passive"))
    )
    (net (code "41") (name "/GPIO39") (class "Default")
      (node (ref "*U1") (pin "35") (pinfunction "MTCK/GPIO39/CLK_OUT3/SUBSPICS1_35") (pintype "passive"))
      (node (ref "j3") (pin "11") (pinfunction "11_11") (pintype "passive"))
    )
    (net (code "42") (name "/GPIO40") (class "Default")
      (node (ref "*U1") (pin "36") (pinfunction "MTDO/GPIO40/CLK_OUT2_36") (pintype "passive"))
      (node (ref "j3") (pin "10") (pinfunction "10_10") (pintype "passive"))
    )
    (net (code "43") (name "/GPIO41") (class "Default")
      (node (ref "*U1") (pin "37") (pinfunction "MTDI/GPIO41/CLK_OUT1_37") (pintype "passive"))
      (node (ref "j3") (pin "9") (pinfunction "9_9") (pintype "passive"))
    )
    (net (code "44") (name "/GPIO42") (class "Default")
      (node (ref "*U1") (pin "38") (pinfunction "MTMS/GPIO42_38") (pintype "passive"))
      (node (ref "j3") (pin "8") (pinfunction "8_8") (pintype "passive"))
    )
    (net (code "45") (name "/GPIO45") (class "Default")
      (node (ref "*U1") (pin "41") (pinfunction "GPIO45_41") (pintype "passive"))
      (node (ref "j3") (pin "5") (pinfunction "5_5") (pintype "passive"))
    )
    (net (code "46") (name "/GPIO46") (class "Default")
      (node (ref "*U1") (pin "44") (pinfunction "GPIO46_44") (pintype "passive"))
      (node (ref "j3") (pin "4") (pinfunction "4_4") (pintype "passive"))
    )
    (net (code "47") (name "/GPIO47") (class "Default")
      (node (ref "*U1") (pin "27") (pinfunction "GPIO47/SPICLK_P_DIFF/SUBSPICLK_P_DIFF_27") (pintype "passive"))
      (node (ref "j3") (pin "23") (pinfunction "23_23") (pintype "passive"))
    )
    (net (code "48") (name "/GPIO48") (class "Default")
      (node (ref "*U1") (pin "30") (pinfunction "GPIO48/SPICLK_N_DIFF/SUBSPICLK_N_DIFF_30") (pintype "passive"))
      (node (ref "j3") (pin "22") (pinfunction "22_22") (pintype "passive"))
    )
    (net (code "49") (name "/RTS_C") (class "Default")
      (node (ref "Q1") (pin "2") (pinfunction "E_2") (pintype "passive"))
      (node (ref "R9") (pin "1") (pinfunction "1_1") (pintype "open_collector"))
      (node (ref "U1") (pin "19") (pinfunction "~{RTS}_19") (pintype "passive"))
    )
    (net (code "50") (name "/RXD_C") (class "Default")
      (node (ref "R23") (pin "1") (pinfunction "1_1") (pintype "open_collector"))
      (node (ref "U1") (pin "1") (pinfunction "RXD_1") (pintype "passive"))
    )
    (net (code "51") (name "/TXD_C") (class "Default")
      (node (ref "R22") (pin "1") (pinfunction "1_1") (pintype "open_collector"))
      (node (ref "U1") (pin "17") (pinfunction "TXD_17") (pintype "passive"))
    )
    (net (code "52") (name "/U0RXD") (class "Default")
      (node (ref "*U1") (pin "40") (pinfunction "U0RXD/GPIO44/CLK_OUT2_40") (pintype "passive"))
      (node (ref "R22") (pin "2") (pinfunction "2_2") (pintype "open_collector"))
      (node (ref "j3") (pin "6") (pinfunction "6_6") (pintype "passive"))
    )
    (net (code "53") (name "/U0TXD") (class "Default")
      (node (ref "*U1") (pin "39") (pinfunction "U0TXD/GPIO43/CLK_OUT1_39") (pintype "passive"))
      (node (ref "R23") (pin "2") (pinfunction "2_2") (pintype "open_collector"))
      (node (ref "j3") (pin "7") (pinfunction "7_7") (pintype "passive"))
    )
    (net (code "54") (name "/USB1_N") (class "Default")
      (node (ref "D2") (pin "2") (pinfunction "2_2") (pintype "open_collector"))
      (node (ref "J1") (pin "A7") (pinfunction "DN1_A7") (pintype "passive"))
      (node (ref "J1") (pin "B7") (pinfunction "DN2_B7") (pintype "passive"))
      (node (ref "R1") (pin "1") (pinfunction "1_1") (pintype "open_collector"))
    )
    (net (code "55") (name "/USB1_P") (class "Default")
      (node (ref "D3") (pin "2") (pinfunction "2_2") (pintype "open_collector"))
      (node (ref "J1") (pin "A6") (pinfunction "DP1_A6") (pintype "passive"))
      (node (ref "J1") (pin "B6") (pinfunction "DP2_B6") (pintype "passive"))
      (node (ref "R2") (pin "1") (pinfunction "1_1") (pintype "open_collector"))
    )
    (net (code "56") (name "/USB2_N") (class "Default")
      (node (ref "D5") (pin "2") (pinfunction "2_2") (pintype "open_collector"))
      (node (ref "J4") (pin "A7") (pinfunction "DN1_A7") (pintype "passive"))
      (node (ref "J4") (pin "B7") (pinfunction "DN2_B7") (pintype "passive"))
      (node (ref "R15") (pin "1") (pinfunction "1_1") (pintype "open_collector"))
    )
    (net (code "57") (name "/USB2_P") (class "Default")
      (node (ref "D6") (pin "2") (pinfunction "2_2") (pintype "open_collector"))
      (node (ref "J4") (pin "A6") (pinfunction "DP1_A6") (pintype "passive"))
      (node (ref "J4") (pin "B6") (pinfunction "DP2_B6") (pintype "passive"))
      (node (ref "R16") (pin "1") (pinfunction "1_1") (pintype "open_collector"))
    )
    (net (code "58") (name "/USBESP32_N") (class "Default")
      (node (ref "*U1") (pin "23") (pinfunction "USB_D-/RTC_GPIO19/GPIO19/U1RTS/ADC2_CH8/CLK_OUT2_23") (pintype "passive"))
      (node (ref "R15") (pin "2") (pinfunction "2_2") (pintype "open_collector"))
      (node (ref "R20") (pin "2") (pinfunction "2_2") (pintype "open_collector"))
    )
    (net (code "59") (name "/USBESP32_P") (class "Default")
      (node (ref "*U1") (pin "24") (pinfunction "USB_D+/RTC_GPIO20/GPIO20/U1CTS/ADC2_CH9/CLK_OUT1_24") (pintype "passive"))
      (node (ref "R16") (pin "2") (pinfunction "2_2") (pintype "open_collector"))
      (node (ref "R19") (pin "2") (pinfunction "2_2") (pintype "open_collector"))
    )
    (net (code "60") (name "GND") (class "Default")
      (node (ref "*U1") (pin "1") (pinfunction "GND_01_1") (pintype "passive"))
      (node (ref "*U1") (pin "2") (pinfunction "GND_02_2") (pintype "passive"))
      (node (ref "*U1") (pin "42") (pinfunction "GND_42_42") (pintype "passive"))
      (node (ref "*U1") (pin "43") (pinfunction "GND_43_43") (pintype "passive"))
      (node (ref "*U1") (pin "46") (pinfunction "GND_46_46") (pintype "passive"))
      (node (ref "*U1") (pin "47") (pinfunction "GND_47_47") (pintype "passive"))
      (node (ref "*U1") (pin "48") (pinfunction "GND_48_48") (pintype "passive"))
      (node (ref "*U1") (pin "49") (pinfunction "GND_49_49") (pintype "passive"))
      (node (ref "*U1") (pin "50") (pinfunction "GND_50_50") (pintype "passive"))
      (node (ref "*U1") (pin "51") (pinfunction "GND_51_51") (pintype "passive"))
      (node (ref "*U1") (pin "52") (pinfunction "GND_52_52") (pintype "passive"))
      (node (ref "*U1") (pin "53") (pinfunction "GND_53_53") (pintype "passive"))
      (node (ref "*U1") (pin "54") (pinfunction "GND_54_54") (pintype "passive"))
      (node (ref "*U1") (pin "55") (pinfunction "GND_55_55") (pintype "passive"))
      (node (ref "*U1") (pin "56") (pinfunction "GND_56_56") (pintype "passive"))
      (node (ref "*U1") (pin "57") (pinfunction "GND_57_57") (pintype "passive"))
      (node (ref "*U1") (pin "58") (pinfunction "GND_58_58") (pintype "passive"))
      (node (ref "*U1") (pin "59") (pinfunction "GND_59_59") (pintype "passive"))
      (node (ref "*U1") (pin "60") (pinfunction "GND_60_60") (pintype "passive"))
      (node (ref "*U1") (pin "61") (pinfunction "GND_61_61") (pintype "passive"))
      (node (ref "*U1") (pin "62") (pinfunction "GND_62_62") (pintype "passive"))
      (node (ref "*U1") (pin "63") (pinfunction "GND_63_63") (pintype "passive"))
      (node (ref "*U1") (pin "64") (pinfunction "GND_64_64") (pintype "passive"))
      (node (ref "*U1") (pin "65") (pinfunction "GND_65_65") (pintype "passive"))
      (node (ref "*U1") (pin "66") (pinfunction "GND_66_66") (pintype "passive"))
      (node (ref "*U1") (pin "67") (pinfunction "GND_67_67") (pintype "passive"))
      (node (ref "*U1") (pin "68") (pinfunction "GND_68_68") (pintype "passive"))
      (node (ref "*U1") (pin "69") (pinfunction "GND_69_69") (pintype "passive"))
      (node (ref "*U1") (pin "70") (pinfunction "GND_70_70") (pintype "passive"))
      (node (ref "*U1") (pin "71") (pinfunction "GND_71_71") (pintype "passive"))
      (node (ref "*U1") (pin "72") (pinfunction "GND_72_72") (pintype "passive"))
      (node (ref "*U1") (pin "73") (pinfunction "GND_73_73") (pintype "passive"))
      (node (ref "C1") (pin "1") (pinfunction "1_1") (pintype "open_collector"))
      (node (ref "C10") (pin "1") (pinfunction "1_1") (pintype "open_collector"))
      (node (ref "C11") (pin "1") (pinfunction "1_1") (pintype "open_collector"))
      (node (ref "C13") (pin "1") (pinfunction "1_1") (pintype "open_collector"))
      (node (ref "C14") (pin "1") (pinfunction "1_1") (pintype "open_collector"))
      (node (ref "C15") (pin "1") (pinfunction "1_1") (pintype "open_collector"))
      (node (ref "C16") (pin "1") (pinfunction "1_1") (pintype "open_collector"))
      (node (ref "C17") (pin "1") (pinfunction "1_1") (pintype "open_collector"))
      (node (ref "C2") (pin "1") (pinfunction "1_1") (pintype "open_collector"))
      (node (ref "C3") (pin "1") (pinfunction "1_1") (pintype "open_collector"))
      (node (ref "C4") (pin "1") (pinfunction "1_1") (pintype "open_collector"))
      (node (ref "C5") (pin "1") (pinfunction "1_1") (pintype "open_collector"))
      (node (ref "C6") (pin "1") (pinfunction "1_1") (pintype "open_collector"))
      (node (ref "C7") (pin "1") (pinfunction "1_1") (pintype "open_collector"))
      (node (ref "C8") (pin "1") (pinfunction "1_1") (pintype "open_collector"))
      (node (ref "C9") (pin "1") (pinfunction "1_1") (pintype "open_collector"))
      (node (ref "D1") (pin "1") (pinfunction "1_1") (pintype "open_collector"))
      (node (ref "D2") (pin "1") (pinfunction "1_1") (pintype "open_collector"))
      (node (ref "D3") (pin "1") (pinfunction "1_1") (pintype "open_collector"))
      (node (ref "D4") (pin "1") (pinfunction "1_1") (pintype "open_collector"))
      (node (ref "D5") (pin "1") (pinfunction "1_1") (pintype "open_collector"))
      (node (ref "D6") (pin "1") (pinfunction "1_1") (pintype "open_collector"))
      (node (ref "D7") (pin "1") (pinfunction "1_1") (pintype "passive"))
      (node (ref "J1") (pin "A1B12") (pinfunction "GND_A1B12_A1B12") (pintype "passive"))
      (node (ref "J1") (pin "B1A12") (pinfunction "GND_B1A12_B1A12") (pintype "passive"))
      (node (ref "J1") (pin "S1") (pinfunction "SHIELD_2_S1") (pintype "passive"))
      (node (ref "J1") (pin "S2") (pinfunction "SHIELD_3_S2") (pintype "passive"))
      (node (ref "J1") (pin "S3") (pinfunction "SHIELD_1_S3") (pintype "passive"))
      (node (ref "J1") (pin "S4") (pinfunction "SHIELD_4_S4") (pintype "passive"))
      (node (ref "J4") (pin "A1B12") (pinfunction "GND_A1B12_A1B12") (pintype "passive"))
      (node (ref "J4") (pin "B1A12") (pinfunction "GND_B1A12_B1A12") (pintype "passive"))
      (node (ref "J4") (pin "S1") (pinfunction "SHIELD_2_S1") (pintype "passive"))
      (node (ref "J4") (pin "S2") (pinfunction "SHIELD_3_S2") (pintype "passive"))
      (node (ref "J4") (pin "S3") (pinfunction "SHIELD_1_S3") (pintype "passive"))
      (node (ref "J4") (pin "S4") (pinfunction "SHIELD_4_S4") (pintype "passive"))
      (node (ref "R10") (pin "1") (pinfunction "1_1") (pintype "open_collector"))
      (node (ref "R11") (pin "1") (pinfunction "1_1") (pintype "open_collector"))
      (node (ref "R4") (pin "1") (pinfunction "1_1") (pintype "open_collector"))
      (node (ref "R5") (pin "1") (pinfunction "1_1") (pintype "open_collector"))
      (node (ref "R6") (pin "1") (pinfunction "1_1") (pintype "open_collector"))
      (node (ref "R7") (pin "1") (pinfunction "1_1") (pintype "open_collector"))
      (node (ref "SW1") (pin "1") (pinfunction "1_1") (pintype "passive"))
      (node (ref "SW1") (pin "2") (pinfunction "2_2") (pintype "passive"))
      (node (ref "SW2") (pin "1") (pinfunction "1_1") (pintype "passive"))
      (node (ref "SW2") (pin "2") (pinfunction "2_2") (pintype "passive"))
      (node (ref "U1") (pin "13") (pinfunction "GND_13") (pintype "passive"))
      (node (ref "U1") (pin "21") (pinfunction "GND_21") (pintype "passive"))
      (node (ref "U1") (pin "3") (pinfunction "GND_3") (pintype "passive"))
      (node (ref "U2") (pin "2") (pinfunction "4_2") (pintype "passive"))
      (node (ref "U2") (pin "4") (pinfunction "GND_4") (pintype "passive"))
      (node (ref "j2") (pin "1") (pinfunction "1_1") (pintype "passive"))
      (node (ref "j2") (pin "23") (pinfunction "23_23") (pintype "passive"))
      (node (ref "j3") (pin "2") (pinfunction "2_2") (pintype "passive"))
      (node (ref "j3") (pin "24") (pinfunction "24_24") (pintype "passive"))
    )
    (net (code "61") (name "Net-(D7-Pad2)") (class "Default")
      (node (ref "D7") (pin "2") (pinfunction "2_2") (pintype "passive"))
      (node (ref "R17") (pin "1") (pinfunction "1_1") (pintype "open_collector"))
    )
    (net (code "62") (name "Net-(D8-Pad2)") (class "Default")
      (node (ref "D8") (pin "2") (pinfunction "2_2") (pintype "passive"))
      (node (ref "R18") (pin "1") (pinfunction "1_1") (pintype "open_collector"))
    )
    (net (code "63") (name "Net-(J1-CC1)") (class "Default")
      (node (ref "J1") (pin "A5") (pinfunction "CC1_A5") (pintype "passive"))
      (node (ref "R6") (pin "2") (pinfunction "2_2") (pintype "open_collector"))
    )
    (net (code "64") (name "Net-(J1-CC2)") (class "Default")
      (node (ref "J1") (pin "B5") (pinfunction "CC2_B5") (pintype "passive"))
      (node (ref "R5") (pin "2") (pinfunction "2_2") (pintype "open_collector"))
    )
    (net (code "65") (name "Net-(J4-CC1)") (class "Default")
      (node (ref "J4") (pin "A5") (pinfunction "CC1_A5") (pintype "passive"))
      (node (ref "R11") (pin "2") (pinfunction "2_2") (pintype "open_collector"))
    )
    (net (code "66") (name "Net-(J4-CC2)") (class "Default")
      (node (ref "J4") (pin "B5") (pinfunction "CC2_B5") (pintype "passive"))
      (node (ref "R10") (pin "2") (pinfunction "2_2") (pintype "open_collector"))
    )
    (net (code "67") (name "Net-(Q1-B)") (class "Default")
      (node (ref "Q1") (pin "1") (pinfunction "B_1") (pintype "passive"))
      (node (ref "R8") (pin "2") (pinfunction "2_2") (pintype "open_collector"))
    )
    (net (code "68") (name "Net-(Q2-B)") (class "Default")
      (node (ref "Q2") (pin "1") (pinfunction "B_1") (pintype "passive"))
      (node (ref "R9") (pin "2") (pinfunction "2_2") (pintype "open_collector"))
    )
    (net (code "69") (name "Net-(U1-3V3OUT)") (class "Default")
      (node (ref "C17") (pin "2") (pinfunction "2_2") (pintype "open_collector"))
      (node (ref "R26") (pin "2") (pinfunction "2_2") (pintype "open_collector"))
      (node (ref "R27") (pin "1") (pinfunction "1_1") (pintype "open_collector"))
      (node (ref "U1") (pin "10") (pinfunction "3V3OUT_10") (pintype "passive"))
      (node (ref "U1") (pin "20") (pinfunction "VCCIO_20") (pintype "passive"))
    )
    (net (code "70") (name "Net-(U1-CBUS0)") (class "Default")
      (node (ref "R7") (pin "2") (pinfunction "2_2") (pintype "open_collector"))
      (node (ref "U1") (pin "15") (pinfunction "CBUS0_15") (pintype "passive"))
    )
    (net (code "71") (name "Net-(U1-CBUS3)") (class "Default")
      (node (ref "R3") (pin "1") (pinfunction "1_1") (pintype "open_collector"))
      (node (ref "R4") (pin "2") (pinfunction "2_2") (pintype "open_collector"))
      (node (ref "U1") (pin "16") (pinfunction "CBUS3_16") (pintype "passive"))
    )
    (net (code "72") (name "Net-(U1-VCC)") (class "Default")
      (node (ref "C1") (pin "2") (pinfunction "2_2") (pintype "open_collector"))
      (node (ref "C2") (pin "2") (pinfunction "2_2") (pintype "open_collector"))
      (node (ref "R24") (pin "2") (pinfunction "2_2") (pintype "open_collector"))
      (node (ref "R25") (pin "2") (pinfunction "2_2") (pintype "open_collector"))
      (node (ref "U1") (pin "12") (pinfunction "VCC_12") (pintype "passive"))
    )
    (net (code "73") (name "Net-(U1-~{RESET})") (class "Default")
      (node (ref "C4") (pin "2") (pinfunction "2_2") (pintype "open_collector"))
      (node (ref "R27") (pin "2") (pinfunction "2_2") (pintype "open_collector"))
      (node (ref "U1") (pin "11") (pinfunction "~{RESET}_11") (pintype "passive"))
    )
    (net (code "74") (name "unconnected-(J1-SBU1-PadA8)") (class "Default")
      (node (ref "J1") (pin "A8") (pinfunction "SBU1_A8") (pintype "passive+no_connect"))
    )
    (net (code "75") (name "unconnected-(J1-SBU2-PadB8)") (class "Default")
      (node (ref "J1") (pin "B8") (pinfunction "SBU2_B8") (pintype "passive+no_connect"))
    )
    (net (code "76") (name "unconnected-(J4-SBU1-PadA8)") (class "Default")
      (node (ref "J4") (pin "A8") (pinfunction "SBU1_A8") (pintype "passive+no_connect"))
    )
    (net (code "77") (name "unconnected-(J4-SBU2-PadB8)") (class "Default")
      (node (ref "J4") (pin "B8") (pinfunction "SBU2_B8") (pintype "passive+no_connect"))
    )
    (net (code "78") (name "unconnected-(U1-CBUS1-Pad14)") (class "Default")
      (node (ref "U1") (pin "14") (pinfunction "CBUS1_14") (pintype "passive+no_connect"))
    )
    (net (code "79") (name "unconnected-(U1-CBUS2-Pad7)") (class "Default")
      (node (ref "U1") (pin "7") (pinfunction "CBUS2_7") (pintype "passive+no_connect"))
    )
    (net (code "80") (name "unconnected-(U1-~{CTS}-Pad6)") (class "Default")
      (node (ref "U1") (pin "6") (pinfunction "~{CTS}_6") (pintype "passive+no_connect"))
    )
    (net (code "81") (name "unconnected-(U1-~{DCD}-Pad5)") (class "Default")
      (node (ref "U1") (pin "5") (pinfunction "~{DCD}_5") (pintype "passive+no_connect"))
    )
    (net (code "82") (name "unconnected-(U1-~{DSR}-Pad4)") (class "Default")
      (node (ref "U1") (pin "4") (pinfunction "~{DSR}_4") (pintype "passive+no_connect"))
    )
    (net (code "83") (name "unconnected-(U1-~{RI}-Pad2)") (class "Default")
      (node (ref "U1") (pin "2") (pinfunction "~{RI}_2") (pintype "passive+no_connect"))
    )
    (net (code "84") (name "unconnected-(j2-Pad24)") (class "Default")
      (node (ref "j2") (pin "24") (pinfunction "24_24") (pintype "passive+no_connect"))
    )
  )
)
